# touchy_feely_lamp.net
KiCad netlist of a schematic drawn in EAGLE
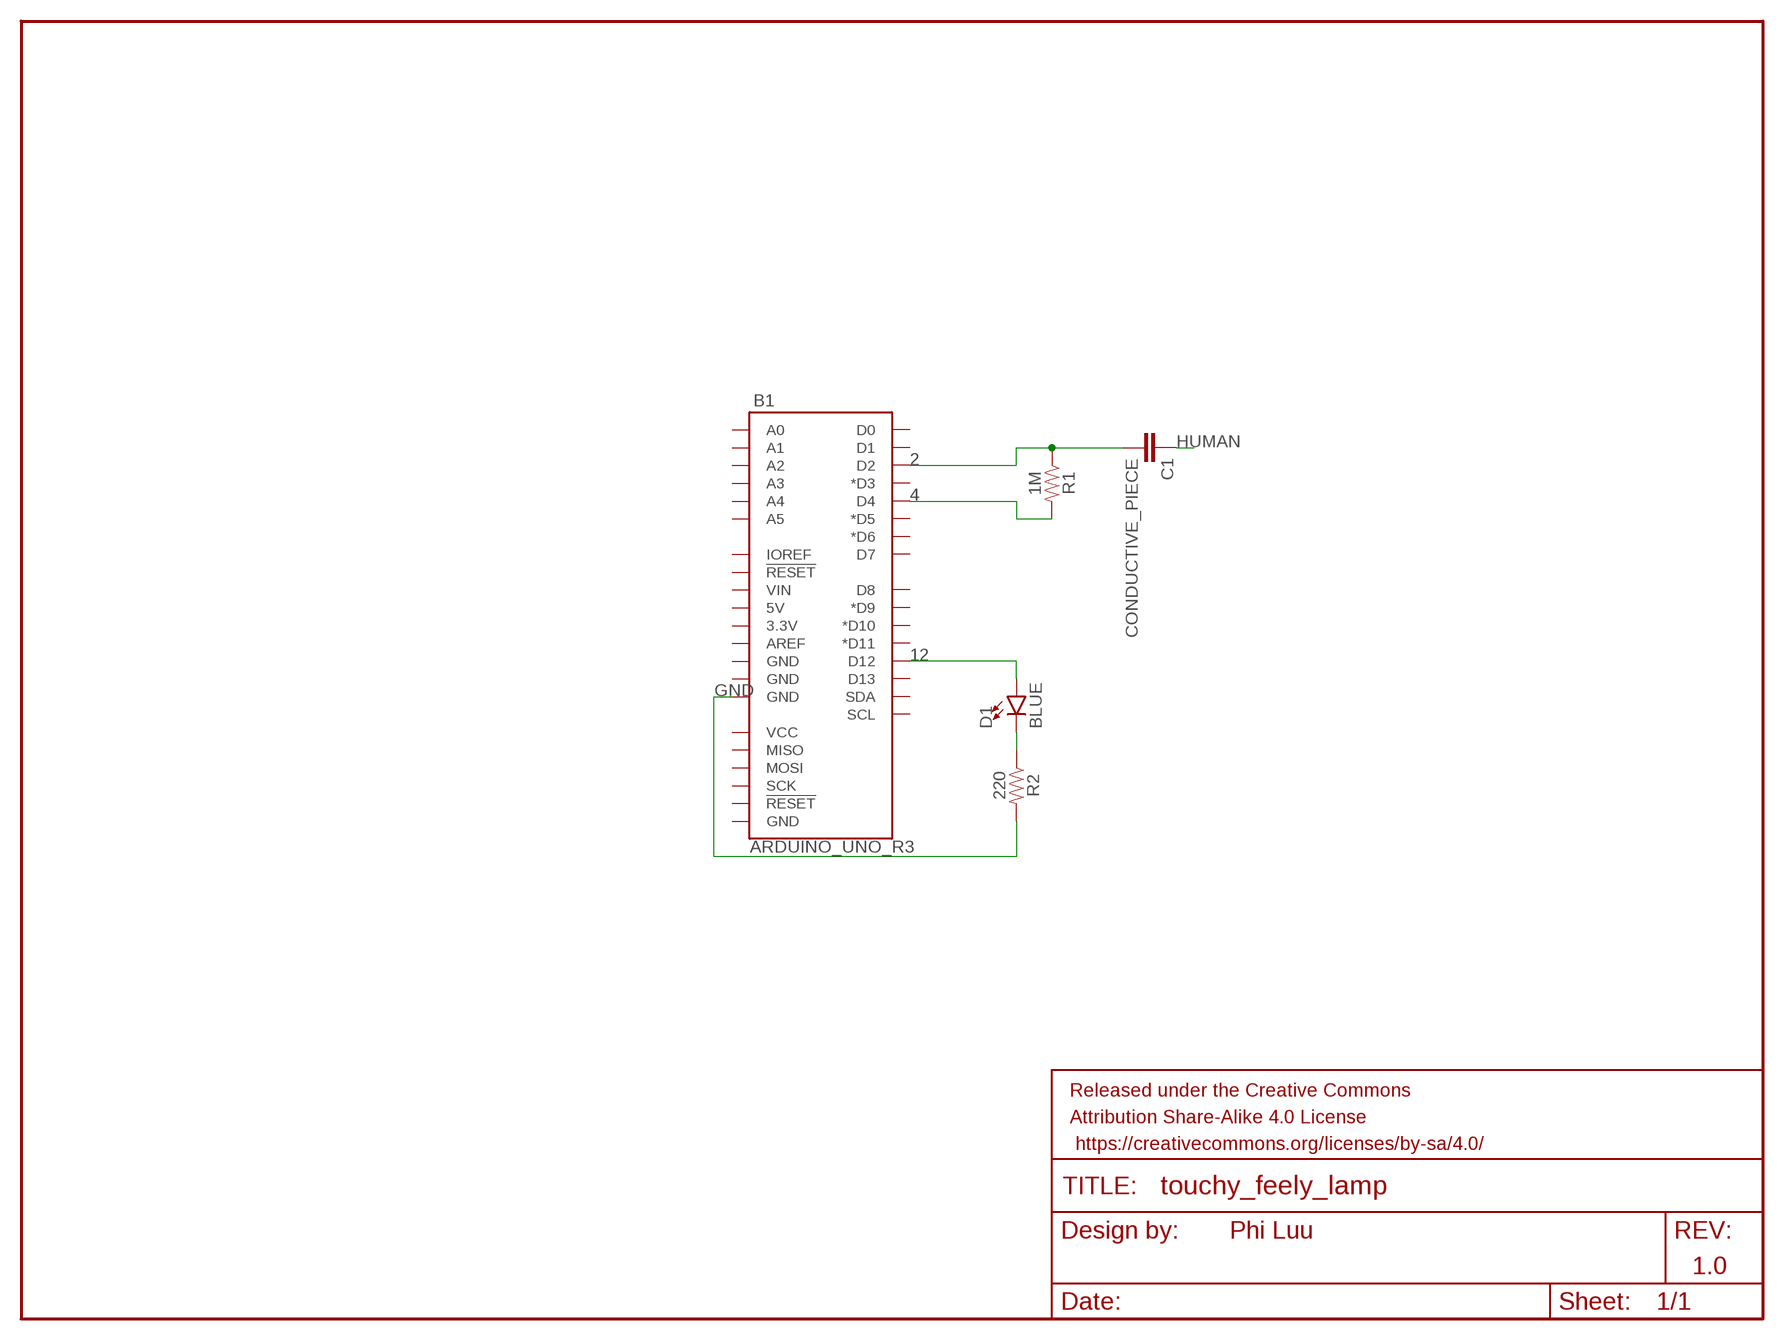
[diagram p0: schematic, sheet 1]

(export (version "E")
  (design (tool "Eeschema 10.0.6"))
  (components
    (comp (ref "B1")
      (value "ARDUINO_UNO_R3")
      (footprint "eagle-import:ARDUINO_R3")
      (libsource (lib "eagle-import") (part "ARDUINO_UNO_R3"))
    )
    (comp (ref "C1")
      (value "CONDUCTIVE_PIECE")
      (footprint "eagle-import:CAP-PTH-2.54")
      (libsource (lib "eagle-import") (part "22PF-PTH-2.54MM-200V-5%"))
    )
    (comp (ref "D1")
      (value "BLUE")
      (footprint "eagle-import:LED_5MM")
      (libsource (lib "eagle-import") (part "LED5MM"))
    )
    (comp (ref "FRAME1")
      (value "FRAME-LETTER")
      (footprint "eagle-import:CREATIVE_COMMONS")
      (libsource (lib "eagle-import") (part "FRAME-LETTER"))
    )
    (comp (ref "R1")
      (value "1M")
      (footprint "eagle-import:AXIAL-0.3")
      (libsource (lib "eagle-import") (part "1MOHM-HORIZ-1/4W-5%"))
    )
    (comp (ref "R2")
      (value "220")
      (footprint "eagle-import:AXIAL-0.3")
      (libsource (lib "eagle-import") (part "1MOHM-HORIZ-1/4W-5%"))
    )
  )
  (nets
    (net (code "1") (name "/2") (class "Default")
      (node (ref "B1") (pin "D2") (pinfunction "D2_D2") (pintype "bidirectional"))
      (node (ref "C1") (pin "2") (pinfunction "2_2") (pintype "passive"))
      (node (ref "R1") (pin "P$1") (pinfunction "1_P$1") (pintype "passive"))
    )
    (net (code "2") (name "/4") (class "Default")
      (node (ref "B1") (pin "D4") (pinfunction "D4_D4") (pintype "bidirectional"))
      (node (ref "R1") (pin "P$2") (pinfunction "2_P$2") (pintype "passive"))
    )
    (net (code "3") (name "/12") (class "Default")
      (node (ref "B1") (pin "D12") (pinfunction "D12_D12") (pintype "bidirectional"))
      (node (ref "D1") (pin "A") (pinfunction "A_A") (pintype "passive"))
    )
    (net (code "4") (name "/GND") (class "Default")
      (node (ref "B1") (pin "GND@2") (pinfunction "GND_GND@2") (pintype "bidirectional"))
      (node (ref "R2") (pin "P$2") (pinfunction "2_P$2") (pintype "passive"))
    )
    (net (code "5") (name "/HUMAN") (class "Default")
      (node (ref "C1") (pin "1") (pinfunction "1_1") (pintype "passive"))
    )
    (net (code "6") (name "Net-(D1-C)") (class "Default")
      (node (ref "D1") (pin "K") (pinfunction "C_K") (pintype "passive"))
      (node (ref "R2") (pin "P$1") (pinfunction "1_P$1") (pintype "passive"))
    )
    (net (code "7") (name "unconnected-(B1-*D3-PadD3)") (class "Default")
      (node (ref "B1") (pin "D3") (pinfunction "*D3_D3") (pintype "bidirectional"))
    )
    (net (code "8") (name "unconnected-(B1-*D5-PadD5)") (class "Default")
      (node (ref "B1") (pin "D5") (pinfunction "*D5_D5") (pintype "bidirectional"))
    )
    (net (code "9") (name "unconnected-(B1-*D6-PadD6)") (class "Default")
      (node (ref "B1") (pin "D6") (pinfunction "*D6_D6") (pintype "bidirectional"))
    )
    (net (code "10") (name "unconnected-(B1-*D9-PadD9)") (class "Default")
      (node (ref "B1") (pin "D9") (pinfunction "*D9_D9") (pintype "bidirectional"))
    )
    (net (code "11") (name "unconnected-(B1-*D10-PadD10)") (class "Default")
      (node (ref "B1") (pin "D10") (pinfunction "*D10_D10") (pintype "bidirectional"))
    )
    (net (code "12") (name "unconnected-(B1-*D11-PadD11)") (class "Default")
      (node (ref "B1") (pin "D11") (pinfunction "*D11_D11") (pintype "bidirectional"))
    )
    (net (code "13") (name "unconnected-(B1-GND-PadGND@1)") (class "Default")
      (node (ref "B1") (pin "GND@1") (pinfunction "GND_GND@1") (pintype "bidirectional"))
    )
    (net (code "14") (name "unconnected-(B1-GND-PadGND@3)") (class "Default")
      (node (ref "B1") (pin "GND@3") (pinfunction "GND_GND@3") (pintype "bidirectional"))
    )
    (net (code "15") (name "unconnected-(B1-GND-PadGND@4)") (class "Default")
      (node (ref "B1") (pin "GND@4") (pinfunction "GND_GND@4") (pintype "bidirectional"))
    )
    (net (code "16") (name "unconnected-(B1-Pad3.3V)") (class "Default")
      (node (ref "B1") (pin "3.3V") (pinfunction "3.3V_3.3V") (pintype "bidirectional"))
    )
    (net (code "17") (name "unconnected-(B1-Pad5V)") (class "Default")
      (node (ref "B1") (pin "5V") (pinfunction "5V_5V") (pintype "bidirectional"))
    )
    (net (code "18") (name "unconnected-(B1-PadA0)") (class "Default")
      (node (ref "B1") (pin "A0") (pinfunction "A0_A0") (pintype "bidirectional"))
    )
    (net (code "19") (name "unconnected-(B1-PadA1)") (class "Default")
      (node (ref "B1") (pin "A1") (pinfunction "A1_A1") (pintype "bidirectional"))
    )
    (net (code "20") (name "unconnected-(B1-PadA2)") (class "Default")
      (node (ref "B1") (pin "A2") (pinfunction "A2_A2") (pintype "bidirectional"))
    )
    (net (code "21") (name "unconnected-(B1-PadA3)") (class "Default")
      (node (ref "B1") (pin "A3") (pinfunction "A3_A3") (pintype "bidirectional"))
    )
    (net (code "22") (name "unconnected-(B1-PadA4)") (class "Default")
      (node (ref "B1") (pin "A4") (pinfunction "A4_A4") (pintype "bidirectional"))
    )
    (net (code "23") (name "unconnected-(B1-PadA5)") (class "Default")
      (node (ref "B1") (pin "A5") (pinfunction "A5_A5") (pintype "bidirectional"))
    )
    (net (code "24") (name "unconnected-(B1-PadAREF)") (class "Default")
      (node (ref "B1") (pin "AREF") (pinfunction "AREF_AREF") (pintype "bidirectional"))
    )
    (net (code "25") (name "unconnected-(B1-PadD0)") (class "Default")
      (node (ref "B1") (pin "D0") (pinfunction "D0_D0") (pintype "bidirectional"))
    )
    (net (code "26") (name "unconnected-(B1-PadD1)") (class "Default")
      (node (ref "B1") (pin "D1") (pinfunction "D1_D1") (pintype "bidirectional"))
    )
    (net (code "27") (name "unconnected-(B1-PadD7)") (class "Default")
      (node (ref "B1") (pin "D7") (pinfunction "D7_D7") (pintype "bidirectional"))
    )
    (net (code "28") (name "unconnected-(B1-PadD8)") (class "Default")
      (node (ref "B1") (pin "D8") (pinfunction "D8_D8") (pintype "bidirectional"))
    )
    (net (code "29") (name "unconnected-(B1-PadD13)") (class "Default")
      (node (ref "B1") (pin "D13") (pinfunction "D13_D13") (pintype "bidirectional"))
    )
    (net (code "30") (name "unconnected-(B1-PadIOREF)") (class "Default")
      (node (ref "B1") (pin "IOREF") (pinfunction "IOREF_IOREF") (pintype "bidirectional"))
    )
    (net (code "31") (name "unconnected-(B1-PadMISO)") (class "Default")
      (node (ref "B1") (pin "MISO") (pinfunction "MISO_MISO") (pintype "bidirectional"))
    )
    (net (code "32") (name "unconnected-(B1-PadMOSI)") (class "Default")
      (node (ref "B1") (pin "MOSI") (pinfunction "MOSI_MOSI") (pintype "bidirectional"))
    )
    (net (code "33") (name "unconnected-(B1-PadSCK)") (class "Default")
      (node (ref "B1") (pin "SCK") (pinfunction "SCK_SCK") (pintype "bidirectional"))
    )
    (net (code "34") (name "unconnected-(B1-PadSCL)") (class "Default")
      (node (ref "B1") (pin "SCL") (pinfunction "SCL_SCL") (pintype "bidirectional"))
    )
    (net (code "35") (name "unconnected-(B1-PadSDA)") (class "Default")
      (node (ref "B1") (pin "SDA") (pinfunction "SDA_SDA") (pintype "bidirectional"))
    )
    (net (code "36") (name "unconnected-(B1-PadVCC)") (class "Default")
      (node (ref "B1") (pin "VCC") (pinfunction "VCC_VCC") (pintype "bidirectional"))
    )
    (net (code "37") (name "unconnected-(B1-PadVIN)") (class "Default")
      (node (ref "B1") (pin "VIN") (pinfunction "VIN_VIN") (pintype "bidirectional"))
    )
    (net (code "38") (name "unconnected-(B1-~{RESET}-PadRESET@1)") (class "Default")
      (node (ref "B1") (pin "RESET@1") (pinfunction "~{RESET}_RESET@1") (pintype "bidirectional"))
    )
    (net (code "39") (name "unconnected-(B1-~{RESET}-PadRESET@2)") (class "Default")
      (node (ref "B1") (pin "RESET@2") (pinfunction "~{RESET}_RESET@2") (pintype "bidirectional"))
    )
  )
)
